# AFE.net
KiCad netlist of a schematic drawn in Altium Designer
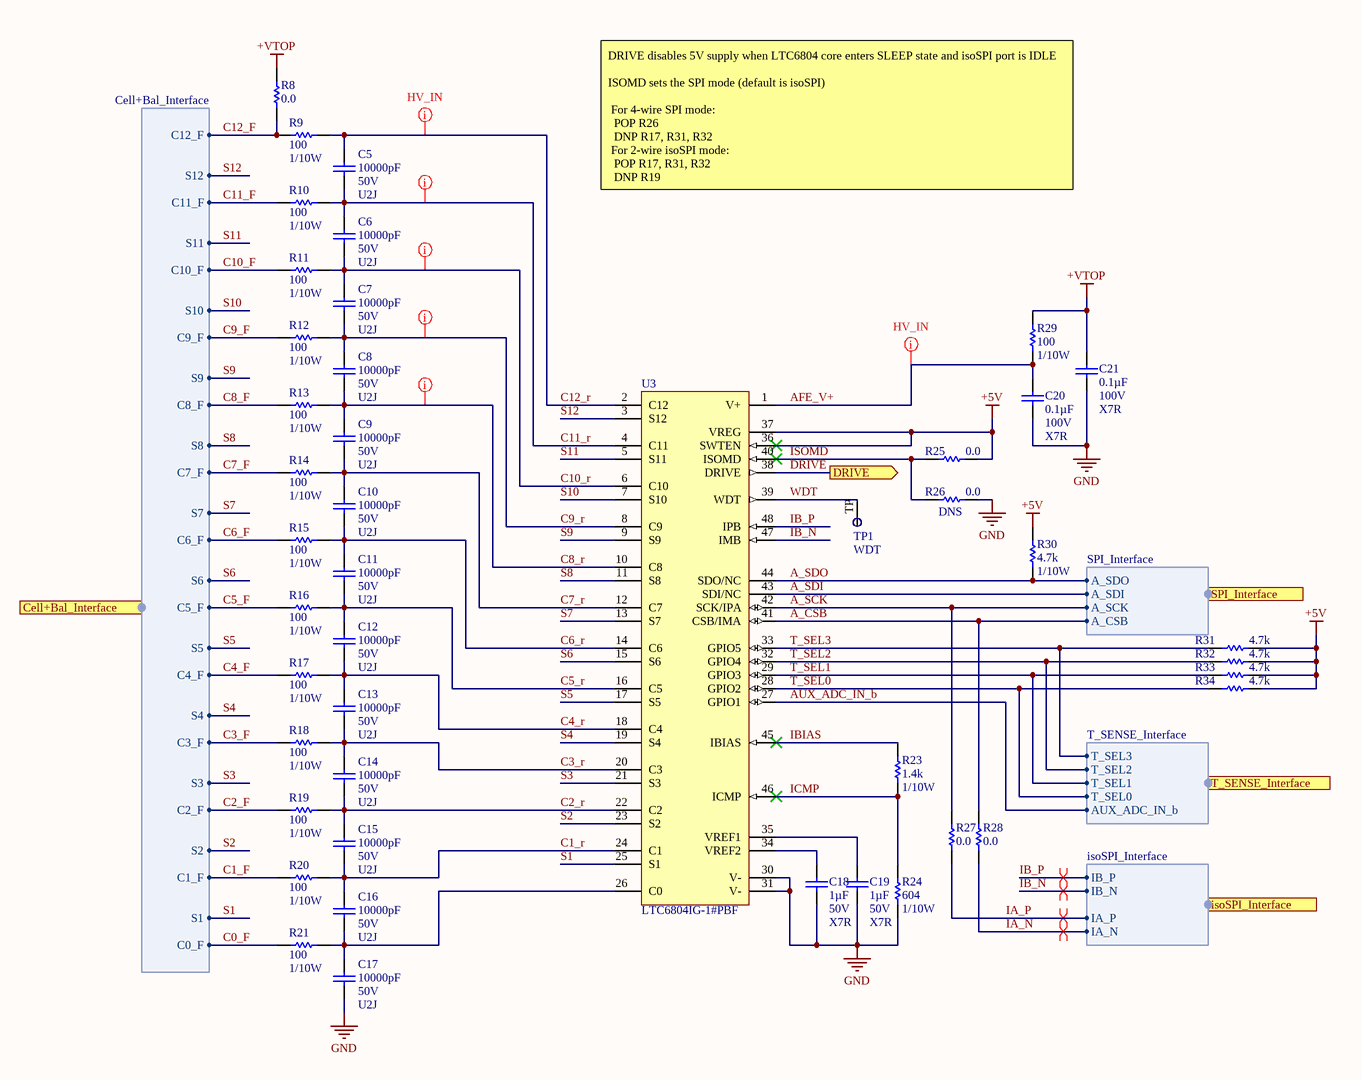
[diagram p0: AFE.SchDoc]

(export (version "E")
  (design (tool "Eeschema 10.0.6"))
  (components
    (comp (ref "C5")
      (value "CAP CER 10nF 50V 5% X7R 0603")
      (footprint "CAP, 0603")
      (description "10000pF ±5% 50V Ceramic Capacitor U2J 0603 (1608 Metric)")
      (fields
        (field (name "TOLERANCE") "±5%")
        (field (name "CAPACITANCE") "10000pF")
        (field (name "VOLTAGE") "50V")
        (field (name "TEMPERATURE COEFFICIENT") "U2J")
      )
      (libsource (lib "Schematic Diagrams") (part "CAP CER 10nF 50V 5% X7R 0603"))
    )
    (comp (ref "C6")
      (value "CAP CER 10nF 50V 5% X7R 0603")
      (footprint "CAP, 0603")
      (description "10000pF ±5% 50V Ceramic Capacitor U2J 0603 (1608 Metric)")
      (fields
        (field (name "TOLERANCE") "±5%")
        (field (name "CAPACITANCE") "10000pF")
        (field (name "VOLTAGE") "50V")
        (field (name "TEMPERATURE COEFFICIENT") "U2J")
      )
      (libsource (lib "Schematic Diagrams") (part "CAP CER 10nF 50V 5% X7R 0603"))
    )
    (comp (ref "C7")
      (value "CAP CER 10nF 50V 5% X7R 0603")
      (footprint "CAP, 0603")
      (description "10000pF ±5% 50V Ceramic Capacitor U2J 0603 (1608 Metric)")
      (fields
        (field (name "TOLERANCE") "±5%")
        (field (name "CAPACITANCE") "10000pF")
        (field (name "VOLTAGE") "50V")
        (field (name "TEMPERATURE COEFFICIENT") "U2J")
      )
      (libsource (lib "Schematic Diagrams") (part "CAP CER 10nF 50V 5% X7R 0603"))
    )
    (comp (ref "C8")
      (value "CAP CER 10nF 50V 5% X7R 0603")
      (footprint "CAP, 0603")
      (description "10000pF ±5% 50V Ceramic Capacitor U2J 0603 (1608 Metric)")
      (fields
        (field (name "TOLERANCE") "±5%")
        (field (name "CAPACITANCE") "10000pF")
        (field (name "VOLTAGE") "50V")
        (field (name "TEMPERATURE COEFFICIENT") "U2J")
      )
      (libsource (lib "Schematic Diagrams") (part "CAP CER 10nF 50V 5% X7R 0603"))
    )
    (comp (ref "C9")
      (value "CAP CER 10nF 50V 5% X7R 0603")
      (footprint "CAP, 0603")
      (description "10000pF ±5% 50V Ceramic Capacitor U2J 0603 (1608 Metric)")
      (fields
        (field (name "TOLERANCE") "±5%")
        (field (name "CAPACITANCE") "10000pF")
        (field (name "VOLTAGE") "50V")
        (field (name "TEMPERATURE COEFFICIENT") "U2J")
      )
      (libsource (lib "Schematic Diagrams") (part "CAP CER 10nF 50V 5% X7R 0603"))
    )
    (comp (ref "C10")
      (value "CAP CER 10nF 50V 5% X7R 0603")
      (footprint "CAP, 0603")
      (description "10000pF ±5% 50V Ceramic Capacitor U2J 0603 (1608 Metric)")
      (fields
        (field (name "TOLERANCE") "±5%")
        (field (name "CAPACITANCE") "10000pF")
        (field (name "VOLTAGE") "50V")
        (field (name "TEMPERATURE COEFFICIENT") "U2J")
      )
      (libsource (lib "Schematic Diagrams") (part "CAP CER 10nF 50V 5% X7R 0603"))
    )
    (comp (ref "C11")
      (value "CAP CER 10nF 50V 5% X7R 0603")
      (footprint "CAP, 0603")
      (description "10000pF ±5% 50V Ceramic Capacitor U2J 0603 (1608 Metric)")
      (fields
        (field (name "TOLERANCE") "±5%")
        (field (name "CAPACITANCE") "10000pF")
        (field (name "VOLTAGE") "50V")
        (field (name "TEMPERATURE COEFFICIENT") "U2J")
      )
      (libsource (lib "Schematic Diagrams") (part "CAP CER 10nF 50V 5% X7R 0603"))
    )
    (comp (ref "C12")
      (value "CAP CER 10nF 50V 5% X7R 0603")
      (footprint "CAP, 0603")
      (description "10000pF ±5% 50V Ceramic Capacitor U2J 0603 (1608 Metric)")
      (fields
        (field (name "TOLERANCE") "±5%")
        (field (name "CAPACITANCE") "10000pF")
        (field (name "VOLTAGE") "50V")
        (field (name "TEMPERATURE COEFFICIENT") "U2J")
      )
      (libsource (lib "Schematic Diagrams") (part "CAP CER 10nF 50V 5% X7R 0603"))
    )
    (comp (ref "C13")
      (value "CAP CER 10nF 50V 5% X7R 0603")
      (footprint "CAP, 0603")
      (description "10000pF ±5% 50V Ceramic Capacitor U2J 0603 (1608 Metric)")
      (fields
        (field (name "TOLERANCE") "±5%")
        (field (name "CAPACITANCE") "10000pF")
        (field (name "VOLTAGE") "50V")
        (field (name "TEMPERATURE COEFFICIENT") "U2J")
      )
      (libsource (lib "Schematic Diagrams") (part "CAP CER 10nF 50V 5% X7R 0603"))
    )
    (comp (ref "C14")
      (value "CAP CER 10nF 50V 5% X7R 0603")
      (footprint "CAP, 0603")
      (description "10000pF ±5% 50V Ceramic Capacitor U2J 0603 (1608 Metric)")
      (fields
        (field (name "TOLERANCE") "±5%")
        (field (name "CAPACITANCE") "10000pF")
        (field (name "VOLTAGE") "50V")
        (field (name "TEMPERATURE COEFFICIENT") "U2J")
      )
      (libsource (lib "Schematic Diagrams") (part "CAP CER 10nF 50V 5% X7R 0603"))
    )
    (comp (ref "C15")
      (value "CAP CER 10nF 50V 5% X7R 0603")
      (footprint "CAP, 0603")
      (description "10000pF ±5% 50V Ceramic Capacitor U2J 0603 (1608 Metric)")
      (fields
        (field (name "TOLERANCE") "±5%")
        (field (name "CAPACITANCE") "10000pF")
        (field (name "VOLTAGE") "50V")
        (field (name "TEMPERATURE COEFFICIENT") "U2J")
      )
      (libsource (lib "Schematic Diagrams") (part "CAP CER 10nF 50V 5% X7R 0603"))
    )
    (comp (ref "C16")
      (value "CAP CER 10nF 50V 5% X7R 0603")
      (footprint "CAP, 0603")
      (description "10000pF ±5% 50V Ceramic Capacitor U2J 0603 (1608 Metric)")
      (fields
        (field (name "TOLERANCE") "±5%")
        (field (name "CAPACITANCE") "10000pF")
        (field (name "VOLTAGE") "50V")
        (field (name "TEMPERATURE COEFFICIENT") "U2J")
      )
      (libsource (lib "Schematic Diagrams") (part "CAP CER 10nF 50V 5% X7R 0603"))
    )
    (comp (ref "C17")
      (value "CAP CER 10nF 50V 5% X7R 0603")
      (footprint "CAP, 0603")
      (description "10000pF ±5% 50V Ceramic Capacitor U2J 0603 (1608 Metric)")
      (fields
        (field (name "TOLERANCE") "±5%")
        (field (name "CAPACITANCE") "10000pF")
        (field (name "VOLTAGE") "50V")
        (field (name "TEMPERATURE COEFFICIENT") "U2J")
      )
      (libsource (lib "Schematic Diagrams") (part "CAP CER 10nF 50V 5% X7R 0603"))
    )
    (comp (ref "C18")
      (value "CAP CER 1UF 50V 10% X7R 0603")
      (footprint "CAP, 0603")
      (description "1µF ±10% 50V Ceramic Capacitor X7R 0603 (1608 Metric)")
      (fields
        (field (name "TOLERANCE") "±10%")
        (field (name "CAPACITANCE") "1µF")
        (field (name "VOLTAGE") "50V")
        (field (name "TEMPERATURE COEFFICIENT") "X7R")
      )
      (libsource (lib "Schematic Diagrams") (part "CAP CER 1UF 50V 10% X7R 0603"))
    )
    (comp (ref "C19")
      (value "CAP CER 1UF 50V 10% X7R 0603")
      (footprint "CAP, 0603")
      (description "1µF ±10% 50V Ceramic Capacitor X7R 0603 (1608 Metric)")
      (fields
        (field (name "TOLERANCE") "±10%")
        (field (name "CAPACITANCE") "1µF")
        (field (name "VOLTAGE") "50V")
        (field (name "TEMPERATURE COEFFICIENT") "X7R")
      )
      (libsource (lib "Schematic Diagrams") (part "CAP CER 1UF 50V 10% X7R 0603"))
    )
    (comp (ref "C20")
      (value "CAP CER 0.1UF 100V 10% X7R 0805")
      (footprint "CAP, 0805")
      (description "0.1µF ±10% 100V Ceramic Capacitor X7R 0805 (2012 Metric)")
      (fields
        (field (name "TOLERANCE") "±10%")
        (field (name "CAPACITANCE") "0.1µF")
        (field (name "VOLTAGE") "100V")
        (field (name "TEMPERATURE COEFFICIENT") "X7R")
      )
      (libsource (lib "Schematic Diagrams") (part "CAP CER 0.1UF 100V 10% X7R 0805"))
    )
    (comp (ref "C21")
      (value "CAP CER 0.1UF 100V 10% X7R 0805")
      (footprint "CAP, 0805")
      (description "0.1µF ±10% 100V Ceramic Capacitor X7R 0805 (2012 Metric)")
      (fields
        (field (name "TOLERANCE") "±10%")
        (field (name "CAPACITANCE") "0.1µF")
        (field (name "VOLTAGE") "100V")
        (field (name "TEMPERATURE COEFFICIENT") "X7R")
      )
      (libsource (lib "Schematic Diagrams") (part "CAP CER 0.1UF 100V 10% X7R 0805"))
    )
    (comp (ref "R8")
      (value "RES 0.0 OHM 1/4W 0603")
      (footprint "RES, 0603")
      (description "RES SMD 0.0 OHM JUMPER 1/4W 0603")
      (fields (field (name "RESISTANCE") "0.0"))
      (libsource (lib "Schematic Diagrams") (part "RES 0.0 OHM 1/4W 0603"))
    )
    (comp (ref "R9")
      (value "RES 100 OHM 1% 1/10W 0603")
      (footprint "RES, 0603")
      (description "100 Ohm ±1% 0.1W, 1/10W Chip Resistor 0603 (1608 Metric) Moisture Resistant Thick Film")
      (fields
        (field (name "TOLERANCE") "±1%")
        (field (name "RESISTANCE") "100")
        (field (name "POWER") "1/10W")
      )
      (libsource (lib "Schematic Diagrams") (part "RES 100 OHM 1% 1/10W 0603"))
    )
    (comp (ref "R10")
      (value "RES 100 OHM 1% 1/10W 0603")
      (footprint "RES, 0603")
      (description "100 Ohm ±1% 0.1W, 1/10W Chip Resistor 0603 (1608 Metric) Moisture Resistant Thick Film")
      (fields
        (field (name "TOLERANCE") "±1%")
        (field (name "RESISTANCE") "100")
        (field (name "POWER") "1/10W")
      )
      (libsource (lib "Schematic Diagrams") (part "RES 100 OHM 1% 1/10W 0603"))
    )
    (comp (ref "R11")
      (value "RES 100 OHM 1% 1/10W 0603")
      (footprint "RES, 0603")
      (description "100 Ohm ±1% 0.1W, 1/10W Chip Resistor 0603 (1608 Metric) Moisture Resistant Thick Film")
      (fields
        (field (name "TOLERANCE") "±1%")
        (field (name "RESISTANCE") "100")
        (field (name "POWER") "1/10W")
      )
      (libsource (lib "Schematic Diagrams") (part "RES 100 OHM 1% 1/10W 0603"))
    )
    (comp (ref "R12")
      (value "RES 100 OHM 1% 1/10W 0603")
      (footprint "RES, 0603")
      (description "100 Ohm ±1% 0.1W, 1/10W Chip Resistor 0603 (1608 Metric) Moisture Resistant Thick Film")
      (fields
        (field (name "TOLERANCE") "±1%")
        (field (name "RESISTANCE") "100")
        (field (name "POWER") "1/10W")
      )
      (libsource (lib "Schematic Diagrams") (part "RES 100 OHM 1% 1/10W 0603"))
    )
    (comp (ref "R13")
      (value "RES 100 OHM 1% 1/10W 0603")
      (footprint "RES, 0603")
      (description "100 Ohm ±1% 0.1W, 1/10W Chip Resistor 0603 (1608 Metric) Moisture Resistant Thick Film")
      (fields
        (field (name "TOLERANCE") "±1%")
        (field (name "RESISTANCE") "100")
        (field (name "POWER") "1/10W")
      )
      (libsource (lib "Schematic Diagrams") (part "RES 100 OHM 1% 1/10W 0603"))
    )
    (comp (ref "R14")
      (value "RES 100 OHM 1% 1/10W 0603")
      (footprint "RES, 0603")
      (description "100 Ohm ±1% 0.1W, 1/10W Chip Resistor 0603 (1608 Metric) Moisture Resistant Thick Film")
      (fields
        (field (name "TOLERANCE") "±1%")
        (field (name "RESISTANCE") "100")
        (field (name "POWER") "1/10W")
      )
      (libsource (lib "Schematic Diagrams") (part "RES 100 OHM 1% 1/10W 0603"))
    )
    (comp (ref "R15")
      (value "RES 100 OHM 1% 1/10W 0603")
      (footprint "RES, 0603")
      (description "100 Ohm ±1% 0.1W, 1/10W Chip Resistor 0603 (1608 Metric) Moisture Resistant Thick Film")
      (fields
        (field (name "TOLERANCE") "±1%")
        (field (name "RESISTANCE") "100")
        (field (name "POWER") "1/10W")
      )
      (libsource (lib "Schematic Diagrams") (part "RES 100 OHM 1% 1/10W 0603"))
    )
    (comp (ref "R16")
      (value "RES 100 OHM 1% 1/10W 0603")
      (footprint "RES, 0603")
      (description "100 Ohm ±1% 0.1W, 1/10W Chip Resistor 0603 (1608 Metric) Moisture Resistant Thick Film")
      (fields
        (field (name "TOLERANCE") "±1%")
        (field (name "RESISTANCE") "100")
        (field (name "POWER") "1/10W")
      )
      (libsource (lib "Schematic Diagrams") (part "RES 100 OHM 1% 1/10W 0603"))
    )
    (comp (ref "R17")
      (value "RES 100 OHM 1% 1/10W 0603")
      (footprint "RES, 0603")
      (description "100 Ohm ±1% 0.1W, 1/10W Chip Resistor 0603 (1608 Metric) Moisture Resistant Thick Film")
      (fields
        (field (name "TOLERANCE") "±1%")
        (field (name "RESISTANCE") "100")
        (field (name "POWER") "1/10W")
      )
      (libsource (lib "Schematic Diagrams") (part "RES 100 OHM 1% 1/10W 0603"))
    )
    (comp (ref "R18")
      (value "RES 100 OHM 1% 1/10W 0603")
      (footprint "RES, 0603")
      (description "100 Ohm ±1% 0.1W, 1/10W Chip Resistor 0603 (1608 Metric) Moisture Resistant Thick Film")
      (fields
        (field (name "TOLERANCE") "±1%")
        (field (name "RESISTANCE") "100")
        (field (name "POWER") "1/10W")
      )
      (libsource (lib "Schematic Diagrams") (part "RES 100 OHM 1% 1/10W 0603"))
    )
    (comp (ref "R19")
      (value "RES 100 OHM 1% 1/10W 0603")
      (footprint "RES, 0603")
      (description "100 Ohm ±1% 0.1W, 1/10W Chip Resistor 0603 (1608 Metric) Moisture Resistant Thick Film")
      (fields
        (field (name "TOLERANCE") "±1%")
        (field (name "RESISTANCE") "100")
        (field (name "POWER") "1/10W")
      )
      (libsource (lib "Schematic Diagrams") (part "RES 100 OHM 1% 1/10W 0603"))
    )
    (comp (ref "R20")
      (value "RES 100 OHM 1% 1/10W 0603")
      (footprint "RES, 0603")
      (description "100 Ohm ±1% 0.1W, 1/10W Chip Resistor 0603 (1608 Metric) Moisture Resistant Thick Film")
      (fields
        (field (name "TOLERANCE") "±1%")
        (field (name "RESISTANCE") "100")
        (field (name "POWER") "1/10W")
      )
      (libsource (lib "Schematic Diagrams") (part "RES 100 OHM 1% 1/10W 0603"))
    )
    (comp (ref "R21")
      (value "RES 100 OHM 1% 1/10W 0603")
      (footprint "RES, 0603")
      (description "100 Ohm ±1% 0.1W, 1/10W Chip Resistor 0603 (1608 Metric) Moisture Resistant Thick Film")
      (fields
        (field (name "TOLERANCE") "±1%")
        (field (name "RESISTANCE") "100")
        (field (name "POWER") "1/10W")
      )
      (libsource (lib "Schematic Diagrams") (part "RES 100 OHM 1% 1/10W 0603"))
    )
    (comp (ref "R23")
      (value "RES 1.4k OHM 1% 1/10W 0603")
      (footprint "RES, 0603")
      (description "RES SMD 1.4K OHM 1% 1/10W 0603")
      (fields
        (field (name "TOLERANCE") "±1%")
        (field (name "RESISTANCE") "1.4k")
        (field (name "POWER") "1/10W")
      )
      (libsource (lib "Schematic Diagrams") (part "RES 1.4k OHM 1% 1/10W 0603"))
    )
    (comp (ref "R24")
      (value "RES 604 OHM 1% 1/10W 0603")
      (footprint "RES, 0603")
      (description "RES SMD 604 OHM 1% 1/10W 0603")
      (fields
        (field (name "TOLERANCE") "±1%")
        (field (name "RESISTANCE") "604")
        (field (name "POWER") "1/10W")
      )
      (libsource (lib "Schematic Diagrams") (part "RES 604 OHM 1% 1/10W 0603"))
    )
    (comp (ref "R25")
      (value "RES 0.0 OHM 1/4W 0603")
      (footprint "RES, 0603")
      (description "RES SMD 0.0 OHM JUMPER 1/4W 0603")
      (fields (field (name "RESISTANCE") "0.0"))
      (libsource (lib "Schematic Diagrams") (part "RES 0.0 OHM 1/4W 0603"))
    )
    (comp (ref "R26")
      (value "RES 0.0 OHM 1/4W 0603")
      (footprint "RES, 0603")
      (description "RES SMD 0.0 OHM JUMPER 1/4W 0603")
      (fields (field (name "RESISTANCE") "0.0") (field (name "DNS") "DNS"))
      (libsource (lib "Schematic Diagrams") (part "RES 0.0 OHM 1/4W 0603"))
    )
    (comp (ref "R27")
      (value "RES 0.0 OHM 1/4W 0603")
      (footprint "RES, 0603")
      (description "RES SMD 0.0 OHM JUMPER 1/4W 0603")
      (fields (field (name "RESISTANCE") "0.0"))
      (libsource (lib "Schematic Diagrams") (part "RES 0.0 OHM 1/4W 0603"))
    )
    (comp (ref "R28")
      (value "RES 0.0 OHM 1/4W 0603")
      (footprint "RES, 0603")
      (description "RES SMD 0.0 OHM JUMPER 1/4W 0603")
      (fields (field (name "RESISTANCE") "0.0"))
      (libsource (lib "Schematic Diagrams") (part "RES 0.0 OHM 1/4W 0603"))
    )
    (comp (ref "R29")
      (value "RES 100 OHM 1% 1/10W 0603")
      (footprint "RES, 0603")
      (description "100 Ohm ±1% 0.1W, 1/10W Chip Resistor 0603 (1608 Metric) Moisture Resistant Thick Film")
      (fields
        (field (name "TOLERANCE") "±1%")
        (field (name "RESISTANCE") "100")
        (field (name "POWER") "1/10W")
      )
      (libsource (lib "Schematic Diagrams") (part "RES 100 OHM 1% 1/10W 0603"))
    )
    (comp (ref "R30")
      (value "RES 4.7K OHM 1% 1/10W 0603")
      (footprint "RES, 0603")
      (description "4.7k Ohm ±1% 0.1W, 1/10W Chip Resistor 0603 (1608 Metric) Moisture Resistant Thick Film")
      (fields
        (field (name "TOLERANCE") "±1%")
        (field (name "RESISTANCE (OHMS)") "4.7k")
        (field (name "POWER (WATTS)") "1/10W")
      )
      (libsource (lib "Schematic Diagrams") (part "RES 4.7K OHM 1% 1/10W 0603"))
    )
    (comp (ref "R31")
      (value "RES 4.7K OHM 1% 1/10W 0603")
      (footprint "RES, 0603")
      (description "4.7k Ohm ±1% 0.1W, 1/10W Chip Resistor 0603 (1608 Metric) Moisture Resistant Thick Film")
      (fields (field (name "TOLERANCE") "±1%") (field (name "RESISTANCE (OHMS)") "4.7k"))
      (libsource (lib "Schematic Diagrams") (part "RES 4.7K OHM 1% 1/10W 0603"))
    )
    (comp (ref "R32")
      (value "RES 4.7K OHM 1% 1/10W 0603")
      (footprint "RES, 0603")
      (description "4.7k Ohm ±1% 0.1W, 1/10W Chip Resistor 0603 (1608 Metric) Moisture Resistant Thick Film")
      (fields (field (name "TOLERANCE") "±1%") (field (name "RESISTANCE (OHMS)") "4.7k"))
      (libsource (lib "Schematic Diagrams") (part "RES 4.7K OHM 1% 1/10W 0603"))
    )
    (comp (ref "R33")
      (value "RES 4.7K OHM 1% 1/10W 0603")
      (footprint "RES, 0603")
      (description "4.7k Ohm ±1% 0.1W, 1/10W Chip Resistor 0603 (1608 Metric) Moisture Resistant Thick Film")
      (fields (field (name "TOLERANCE") "±1%") (field (name "RESISTANCE (OHMS)") "4.7k"))
      (libsource (lib "Schematic Diagrams") (part "RES 4.7K OHM 1% 1/10W 0603"))
    )
    (comp (ref "R34")
      (value "RES 4.7K OHM 1% 1/10W 0603")
      (footprint "RES, 0603")
      (description "4.7k Ohm ±1% 0.1W, 1/10W Chip Resistor 0603 (1608 Metric) Moisture Resistant Thick Film")
      (fields (field (name "TOLERANCE") "±1%") (field (name "RESISTANCE (OHMS)") "4.7k"))
      (libsource (lib "Schematic Diagrams") (part "RES 4.7K OHM 1% 1/10W 0603"))
    )
    (comp (ref "TP1")
      (value "WDT")
      (footprint "Test Point")
      (libsource (lib "Schematic Diagrams") (part "Test Point"))
    )
    (comp (ref "U3")
      (value "IC MONITOR BATT STACK 48SSOP")
      (footprint "SSOP50P780X200-48N")
      (description "Battery Battery Monitor IC Multi-Chemistry 48-SSOP")
      (fields (field (name "MANUFACTURER PART NUMBER 1") "LTC6804IG-1#PBF"))
      (libsource (lib "Schematic Diagrams") (part "IC MONITOR BATT STACK 48SSOP"))
    )
  )
  (nets
    (net (code "5") (name "+5V") (class "Default")
      (node (ref "R25") (pin "2") (pinfunction "2_2") (pintype "passive"))
      (node (ref "R30") (pin "1") (pinfunction "1_1") (pintype "passive"))
      (node (ref "R31") (pin "2") (pinfunction "2_2") (pintype "passive"))
      (node (ref "R32") (pin "2") (pinfunction "2_2") (pintype "passive"))
      (node (ref "R33") (pin "2") (pinfunction "2_2") (pintype "passive"))
      (node (ref "R34") (pin "2") (pinfunction "2_2") (pintype "passive"))
      (node (ref "U3") (pin "36") (pinfunction "SWTEN_36") (pintype "input"))
      (node (ref "U3") (pin "37") (pinfunction "VREG_37") (pintype "power_in"))
    )
    (net (code "6") (name "+VTOP") (class "Default")
      (node (ref "C21") (pin "1") (pinfunction "1_1") (pintype "passive"))
      (node (ref "R29") (pin "1") (pinfunction "1_1") (pintype "passive"))
      (node (ref "R8") (pin "1") (pinfunction "1_1") (pintype "passive"))
    )
    (net (code "7") (name "/AFE_V+") (class "Default")
      (node (ref "C20") (pin "1") (pinfunction "1_1") (pintype "passive"))
      (node (ref "R29") (pin "2") (pinfunction "2_2") (pintype "passive"))
      (node (ref "U3") (pin "1") (pinfunction "V+_1") (pintype "power_in"))
    )
    (net (code "8") (name "/AUX_ADC_IN_b") (class "Default")
      (node (ref "U3") (pin "27") (pinfunction "GPIO1_27") (pintype "bidirectional"))
    )
    (net (code "9") (name "/A_CSB") (class "Default")
      (node (ref "R28") (pin "1") (pinfunction "1_1") (pintype "passive"))
      (node (ref "U3") (pin "41") (pinfunction "CSB/IMA_41") (pintype "bidirectional"))
    )
    (net (code "10") (name "/A_SCK") (class "Default")
      (node (ref "R27") (pin "1") (pinfunction "1_1") (pintype "passive"))
      (node (ref "U3") (pin "42") (pinfunction "SCK/IPA_42") (pintype "bidirectional"))
    )
    (net (code "11") (name "/A_SDI") (class "Default")
      (node (ref "U3") (pin "43") (pinfunction "SDI/NC_43") (pintype "passive"))
    )
    (net (code "12") (name "/A_SDO") (class "Default")
      (node (ref "R30") (pin "2") (pinfunction "2_2") (pintype "passive"))
      (node (ref "U3") (pin "44") (pinfunction "SDO/NC_44") (pintype "passive"))
    )
    (net (code "13") (name "/C0_F") (class "Default")
      (node (ref "R21") (pin "1") (pinfunction "1_1") (pintype "passive"))
    )
    (net (code "14") (name "/C1_F") (class "Default")
      (node (ref "R20") (pin "1") (pinfunction "1_1") (pintype "passive"))
    )
    (net (code "15") (name "/C1_r") (class "Default")
      (node (ref "C15") (pin "2") (pinfunction "2_2") (pintype "passive"))
      (node (ref "C16") (pin "1") (pinfunction "1_1") (pintype "passive"))
      (node (ref "R20") (pin "2") (pinfunction "2_2") (pintype "passive"))
      (node (ref "U3") (pin "24") (pinfunction "C1_24") (pintype "passive"))
    )
    (net (code "16") (name "/C2_F") (class "Default")
      (node (ref "R19") (pin "1") (pinfunction "1_1") (pintype "passive"))
    )
    (net (code "17") (name "/C2_r") (class "Default")
      (node (ref "C14") (pin "2") (pinfunction "2_2") (pintype "passive"))
      (node (ref "C15") (pin "1") (pinfunction "1_1") (pintype "passive"))
      (node (ref "R19") (pin "2") (pinfunction "2_2") (pintype "passive"))
      (node (ref "U3") (pin "22") (pinfunction "C2_22") (pintype "passive"))
    )
    (net (code "18") (name "/C3_F") (class "Default")
      (node (ref "R18") (pin "1") (pinfunction "1_1") (pintype "passive"))
    )
    (net (code "19") (name "/C3_r") (class "Default")
      (node (ref "C13") (pin "2") (pinfunction "2_2") (pintype "passive"))
      (node (ref "C14") (pin "1") (pinfunction "1_1") (pintype "passive"))
      (node (ref "R18") (pin "2") (pinfunction "2_2") (pintype "passive"))
      (node (ref "U3") (pin "20") (pinfunction "C3_20") (pintype "passive"))
    )
    (net (code "20") (name "/C4_F") (class "Default")
      (node (ref "R17") (pin "1") (pinfunction "1_1") (pintype "passive"))
    )
    (net (code "21") (name "/C4_r") (class "Default")
      (node (ref "C12") (pin "2") (pinfunction "2_2") (pintype "passive"))
      (node (ref "C13") (pin "1") (pinfunction "1_1") (pintype "passive"))
      (node (ref "R17") (pin "2") (pinfunction "2_2") (pintype "passive"))
      (node (ref "U3") (pin "18") (pinfunction "C4_18") (pintype "passive"))
    )
    (net (code "22") (name "/C5_F") (class "Default")
      (node (ref "R16") (pin "1") (pinfunction "1_1") (pintype "passive"))
    )
    (net (code "23") (name "/C5_r") (class "Default")
      (node (ref "C11") (pin "2") (pinfunction "2_2") (pintype "passive"))
      (node (ref "C12") (pin "1") (pinfunction "1_1") (pintype "passive"))
      (node (ref "R16") (pin "2") (pinfunction "2_2") (pintype "passive"))
      (node (ref "U3") (pin "16") (pinfunction "C5_16") (pintype "passive"))
    )
    (net (code "24") (name "/C6_F") (class "Default")
      (node (ref "R15") (pin "1") (pinfunction "1_1") (pintype "passive"))
    )
    (net (code "25") (name "/C6_r") (class "Default")
      (node (ref "C10") (pin "2") (pinfunction "2_2") (pintype "passive"))
      (node (ref "C11") (pin "1") (pinfunction "1_1") (pintype "passive"))
      (node (ref "R15") (pin "2") (pinfunction "2_2") (pintype "passive"))
      (node (ref "U3") (pin "14") (pinfunction "C6_14") (pintype "passive"))
    )
    (net (code "26") (name "/C7_F") (class "Default")
      (node (ref "R14") (pin "1") (pinfunction "1_1") (pintype "passive"))
    )
    (net (code "27") (name "/C7_r") (class "Default")
      (node (ref "C10") (pin "1") (pinfunction "1_1") (pintype "passive"))
      (node (ref "C9") (pin "2") (pinfunction "2_2") (pintype "passive"))
      (node (ref "R14") (pin "2") (pinfunction "2_2") (pintype "passive"))
      (node (ref "U3") (pin "12") (pinfunction "C7_12") (pintype "passive"))
    )
    (net (code "28") (name "/C8_F") (class "Default")
      (node (ref "R13") (pin "1") (pinfunction "1_1") (pintype "passive"))
    )
    (net (code "29") (name "/C8_r") (class "Default")
      (node (ref "C8") (pin "2") (pinfunction "2_2") (pintype "passive"))
      (node (ref "C9") (pin "1") (pinfunction "1_1") (pintype "passive"))
      (node (ref "R13") (pin "2") (pinfunction "2_2") (pintype "passive"))
      (node (ref "U3") (pin "10") (pinfunction "C8_10") (pintype "passive"))
    )
    (net (code "30") (name "/C9_F") (class "Default")
      (node (ref "R12") (pin "1") (pinfunction "1_1") (pintype "passive"))
    )
    (net (code "31") (name "/C9_r") (class "Default")
      (node (ref "C7") (pin "2") (pinfunction "2_2") (pintype "passive"))
      (node (ref "C8") (pin "1") (pinfunction "1_1") (pintype "passive"))
      (node (ref "R12") (pin "2") (pinfunction "2_2") (pintype "passive"))
      (node (ref "U3") (pin "8") (pinfunction "C9_8") (pintype "passive"))
    )
    (net (code "32") (name "/C10_F") (class "Default")
      (node (ref "R11") (pin "1") (pinfunction "1_1") (pintype "passive"))
    )
    (net (code "33") (name "/C10_r") (class "Default")
      (node (ref "C6") (pin "2") (pinfunction "2_2") (pintype "passive"))
      (node (ref "C7") (pin "1") (pinfunction "1_1") (pintype "passive"))
      (node (ref "R11") (pin "2") (pinfunction "2_2") (pintype "passive"))
      (node (ref "U3") (pin "6") (pinfunction "C10_6") (pintype "passive"))
    )
    (net (code "34") (name "/C11_F") (class "Default")
      (node (ref "R10") (pin "1") (pinfunction "1_1") (pintype "passive"))
    )
    (net (code "35") (name "/C11_r") (class "Default")
      (node (ref "C5") (pin "2") (pinfunction "2_2") (pintype "passive"))
      (node (ref "C6") (pin "1") (pinfunction "1_1") (pintype "passive"))
      (node (ref "R10") (pin "2") (pinfunction "2_2") (pintype "passive"))
      (node (ref "U3") (pin "4") (pinfunction "C11_4") (pintype "passive"))
    )
    (net (code "36") (name "/C12_F") (class "Default")
      (node (ref "R8") (pin "2") (pinfunction "2_2") (pintype "passive"))
      (node (ref "R9") (pin "1") (pinfunction "1_1") (pintype "passive"))
    )
    (net (code "37") (name "/C12_r") (class "Default")
      (node (ref "C5") (pin "1") (pinfunction "1_1") (pintype "passive"))
      (node (ref "R9") (pin "2") (pinfunction "2_2") (pintype "passive"))
      (node (ref "U3") (pin "2") (pinfunction "C12_2") (pintype "passive"))
    )
    (net (code "38") (name "/DRIVE") (class "Default")
      (node (ref "U3") (pin "38") (pinfunction "DRIVE_38") (pintype "output"))
    )
    (net (code "39") (name "/IA_N") (class "Default")
      (node (ref "R28") (pin "2") (pinfunction "2_2") (pintype "passive"))
    )
    (net (code "40") (name "/IA_P") (class "Default")
      (node (ref "R27") (pin "2") (pinfunction "2_2") (pintype "passive"))
    )
    (net (code "41") (name "/IBIAS") (class "Default")
      (node (ref "R23") (pin "1") (pinfunction "1_1") (pintype "passive"))
      (node (ref "U3") (pin "45") (pinfunction "IBIAS_45") (pintype "input"))
    )
    (net (code "42") (name "/IB_N") (class "Default")
      (node (ref "U3") (pin "47") (pinfunction "IMB_47") (pintype "input"))
    )
    (net (code "43") (name "/IB_P") (class "Default")
      (node (ref "U3") (pin "48") (pinfunction "IPB_48") (pintype "input"))
    )
    (net (code "44") (name "/ICMP") (class "Default")
      (node (ref "R23") (pin "2") (pinfunction "2_2") (pintype "passive"))
      (node (ref "R24") (pin "1") (pinfunction "1_1") (pintype "passive"))
      (node (ref "U3") (pin "46") (pinfunction "ICMP_46") (pintype "input"))
    )
    (net (code "45") (name "/ISOMD") (class "Default")
      (node (ref "R25") (pin "1") (pinfunction "1_1") (pintype "passive"))
      (node (ref "R26") (pin "1") (pinfunction "1_1") (pintype "passive"))
      (node (ref "U3") (pin "40") (pinfunction "ISOMD_40") (pintype "input"))
    )
    (net (code "46") (name "/S1") (class "Default")
      (node (ref "U3") (pin "25") (pinfunction "S1_25") (pintype "passive"))
    )
    (net (code "47") (name "/S2") (class "Default")
      (node (ref "U3") (pin "23") (pinfunction "S2_23") (pintype "passive"))
    )
    (net (code "48") (name "/S3") (class "Default")
      (node (ref "U3") (pin "21") (pinfunction "S3_21") (pintype "passive"))
    )
    (net (code "49") (name "/S4") (class "Default")
      (node (ref "U3") (pin "19") (pinfunction "S4_19") (pintype "passive"))
    )
    (net (code "50") (name "/S5") (class "Default")
      (node (ref "U3") (pin "17") (pinfunction "S5_17") (pintype "passive"))
    )
    (net (code "51") (name "/S6") (class "Default")
      (node (ref "U3") (pin "15") (pinfunction "S6_15") (pintype "passive"))
    )
    (net (code "52") (name "/S7") (class "Default")
      (node (ref "U3") (pin "13") (pinfunction "S7_13") (pintype "passive"))
    )
    (net (code "53") (name "/S8") (class "Default")
      (node (ref "U3") (pin "11") (pinfunction "S8_11") (pintype "passive"))
    )
    (net (code "54") (name "/S9") (class "Default")
      (node (ref "U3") (pin "9") (pinfunction "S9_9") (pintype "passive"))
    )
    (net (code "55") (name "/S10") (class "Default")
      (node (ref "U3") (pin "7") (pinfunction "S10_7") (pintype "passive"))
    )
    (net (code "56") (name "/S11") (class "Default")
      (node (ref "U3") (pin "5") (pinfunction "S11_5") (pintype "passive"))
    )
    (net (code "57") (name "/S12") (class "Default")
      (node (ref "U3") (pin "3") (pinfunction "S12_3") (pintype "passive"))
    )
    (net (code "58") (name "/T_SEL0") (class "Default")
      (node (ref "R34") (pin "1") (pinfunction "1_1") (pintype "passive"))
      (node (ref "U3") (pin "28") (pinfunction "GPIO2_28") (pintype "bidirectional"))
    )
    (net (code "59") (name "/T_SEL1") (class "Default")
      (node (ref "R33") (pin "1") (pinfunction "1_1") (pintype "passive"))
      (node (ref "U3") (pin "29") (pinfunction "GPIO3_29") (pintype "bidirectional"))
    )
    (net (code "60") (name "/T_SEL2") (class "Default")
      (node (ref "R32") (pin "1") (pinfunction "1_1") (pintype "passive"))
      (node (ref "U3") (pin "32") (pinfunction "GPIO4_32") (pintype "bidirectional"))
    )
    (net (code "61") (name "/T_SEL3") (class "Default")
      (node (ref "R31") (pin "1") (pinfunction "1_1") (pintype "passive"))
      (node (ref "U3") (pin "33") (pinfunction "GPIO5_33") (pintype "bidirectional"))
    )
    (net (code "62") (name "/WDT") (class "Default")
      (node (ref "TP1") (pin "TP") (pinfunction "1_TP") (pintype "passive"))
      (node (ref "U3") (pin "39") (pinfunction "WDT_39") (pintype "output"))
    )
    (net (code "67") (name "GND") (class "Default")
      (node (ref "C17") (pin "2") (pinfunction "2_2") (pintype "passive"))
      (node (ref "C18") (pin "2") (pinfunction "2_2") (pintype "passive"))
      (node (ref "C19") (pin "2") (pinfunction "2_2") (pintype "passive"))
      (node (ref "C20") (pin "2") (pinfunction "2_2") (pintype "passive"))
      (node (ref "C21") (pin "2") (pinfunction "2_2") (pintype "passive"))
      (node (ref "R24") (pin "2") (pinfunction "2_2") (pintype "passive"))
      (node (ref "R26") (pin "2") (pinfunction "2_2") (pintype "passive"))
      (node (ref "U3") (pin "30") (pinfunction "V-_30") (pintype "power_in"))
      (node (ref "U3") (pin "31") (pinfunction "V-_31") (pintype "power_in"))
    )
    (net (code "68") (name "Net-(U3-C0)") (class "Default")
      (node (ref "C16") (pin "2") (pinfunction "2_2") (pintype "passive"))
      (node (ref "C17") (pin "1") (pinfunction "1_1") (pintype "passive"))
      (node (ref "R21") (pin "2") (pinfunction "2_2") (pintype "passive"))
      (node (ref "U3") (pin "26") (pinfunction "C0_26") (pintype "passive"))
    )
    (net (code "69") (name "Net-(U3-VREF1)") (class "Default")
      (node (ref "C19") (pin "1") (pinfunction "1_1") (pintype "passive"))
      (node (ref "U3") (pin "35") (pinfunction "VREF1_35") (pintype "power_in"))
    )
    (net (code "70") (name "Net-(U3-VREF2)") (class "Default")
      (node (ref "C18") (pin "1") (pinfunction "1_1") (pintype "passive"))
      (node (ref "U3") (pin "34") (pinfunction "VREF2_34") (pintype "power_in"))
    )
  )
)
